# DigitalOut.net
KiCad netlist of a schematic drawn in Altium Designer
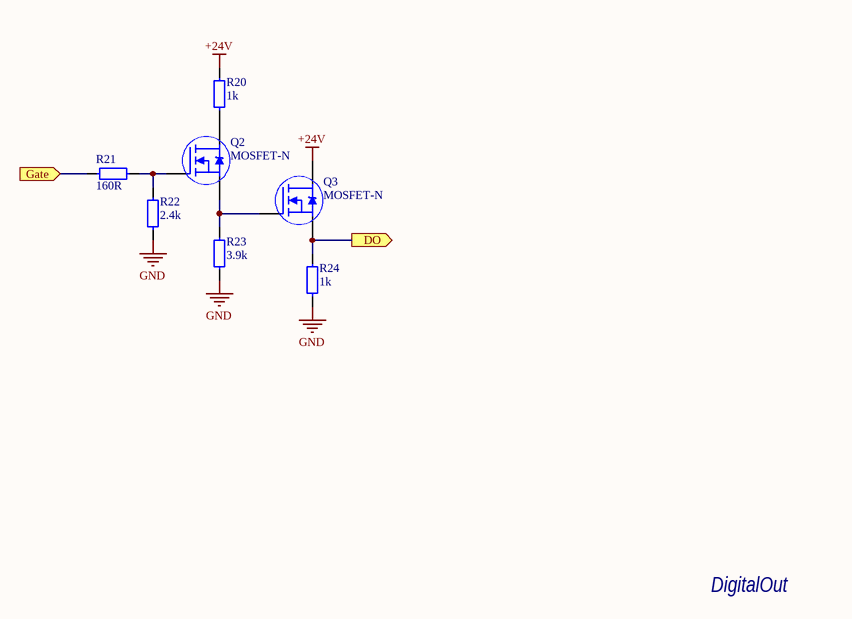
[diagram p0: DigitalOut.SchDoc]

(export (version "E")
  (design (tool "Eeschema 10.0.6"))
  (components
    (comp (ref "Q2")
      (value "MOSFET-N")
      (footprint "SOT-23")
      (description "VDS 30V,  VGS Max ± 20V, RDS 27-40mΩ,")
      (fields
        (field (name "PART NUMBER") "IRLML0030TRPBF")
        (field (name "MANUFACTURER") "Infineon Technologies")
      )
      (libsource (lib "БУНЭ") (part "MOSFET-N [IRLML]"))
    )
    (comp (ref "Q3")
      (value "MOSFET-N")
      (footprint "SOT-23")
      (description "VDS 30V,  VGS Max ± 20V, RDS 27-40mΩ,")
      (fields
        (field (name "PART NUMBER") "IRLML0030TRPBF")
        (field (name "MANUFACTURER") "Infineon Technologies")
      )
      (libsource (lib "БУНЭ") (part "MOSFET-N [IRLML]"))
    )
    (comp (ref "R20")
      (value "1k")
      (footprint "0603 Resistor")
      (description "0.1W 0603 1k, 1%")
      (fields (field (name "PART NUMBER") "RC0603FR-071KL") (field (name "MANUFACTURER") "Taiwan"))
      (libsource (lib "БУНЭ") (part "Res 1k (0603)"))
    )
    (comp (ref "R21")
      (value "160R")
      (footprint "0603 Resistor")
      (description "0.1W 0603 160R, 1%")
      (fields (field (name "PART NUMBER") "RC0603FR-07160RL") (field (name "MANUFACTURER") "Taiwan"))
      (libsource (lib "БУС") (part "Res 160R (0603)"))
    )
    (comp (ref "R22")
      (value "2.4k")
      (footprint "0603 Resistor")
      (description "0.1W 0603 2.4k, 1%")
      (fields (field (name "PART NUMBER") "RC0603FR-072K4L") (field (name "MANUFACTURER") "Taiwan"))
      (libsource (lib "БУС") (part "Res 2.4k (0603)"))
    )
    (comp (ref "R23")
      (value "3.9k")
      (footprint "0603 Resistor")
      (description "0.1W 0603 3.9k, 1%")
      (fields (field (name "PART NUMBER") "RC0603FR-073K9L") (field (name "MANUFACTURER") "Taiwan"))
      (libsource (lib "БУНЭ") (part "Res 3.9k (0603)"))
    )
    (comp (ref "R24")
      (value "1k")
      (footprint "0603 Resistor")
      (description "0.1W 0603 1k, 1%")
      (fields (field (name "PART NUMBER") "RC0603FR-071KL") (field (name "MANUFACTURER") "Taiwan"))
      (libsource (lib "БУНЭ") (part "Res 1k (0603)"))
    )
  )
  (nets
    (net (code "1") (name "+24V") (class "Default")
      (node (ref "Q3") (pin "3") (pinfunction "Drain_3") (pintype "passive"))
      (node (ref "R20") (pin "2") (pinfunction "2_2") (pintype "passive"))
    )
    (net (code "2") (name "/DO") (class "Default")
      (node (ref "Q3") (pin "2") (pinfunction "Source_2") (pintype "passive"))
      (node (ref "R24") (pin "2") (pinfunction "2_2") (pintype "passive"))
    )
    (net (code "3") (name "/Gate") (class "Default")
      (node (ref "R21") (pin "1") (pinfunction "1_1") (pintype "passive"))
    )
    (net (code "4") (name "GND") (class "Default")
      (node (ref "R22") (pin "1") (pinfunction "1_1") (pintype "passive"))
      (node (ref "R23") (pin "1") (pinfunction "1_1") (pintype "passive"))
      (node (ref "R24") (pin "1") (pinfunction "1_1") (pintype "passive"))
    )
    (net (code "5") (name "Net-(Q2-Drain)") (class "Default")
      (node (ref "Q2") (pin "3") (pinfunction "Drain_3") (pintype "passive"))
      (node (ref "R20") (pin "1") (pinfunction "1_1") (pintype "passive"))
    )
    (net (code "6") (name "Net-(Q2-Gate)") (class "Default")
      (node (ref "Q2") (pin "1") (pinfunction "Gate_1") (pintype "passive"))
      (node (ref "R21") (pin "2") (pinfunction "2_2") (pintype "passive"))
      (node (ref "R22") (pin "2") (pinfunction "2_2") (pintype "passive"))
    )
    (net (code "7") (name "Net-(Q2-Source)") (class "Default")
      (node (ref "Q2") (pin "2") (pinfunction "Source_2") (pintype "passive"))
      (node (ref "Q3") (pin "1") (pinfunction "Gate_1") (pintype "passive"))
      (node (ref "R23") (pin "2") (pinfunction "2_2") (pintype "passive"))
    )
  )
)
